# Measurement_board.net
KiCad netlist of a schematic drawn in Altium Designer
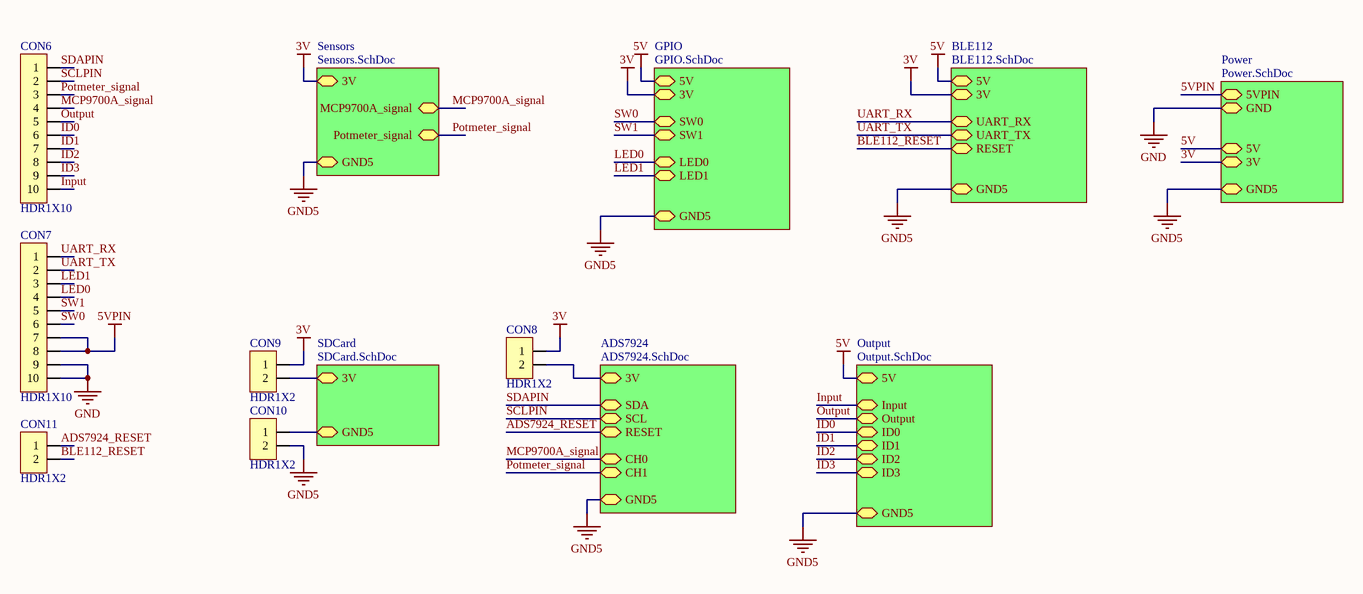
[diagram p0: Measurement_board.SchDoc]

(export (version "E")
  (design (tool "Eeschema 10.0.6"))
  (components
    (comp (ref "CON6")
      (value "HDR1X10")
      (footprint "dimploma:HDR1X10RAST")
      (libsource (lib "diploma") (part "HDR1X10"))
    )
    (comp (ref "CON7")
      (value "HDR1X10")
      (footprint "dimploma:HDR1X10RAST")
      (libsource (lib "diploma") (part "HDR1X10"))
    )
    (comp (ref "CON8")
      (value "HDR1X2")
      (footprint "dimploma:HDR1X2RAST")
      (libsource (lib "diploma") (part "HDR1X2"))
    )
    (comp (ref "CON9")
      (value "HDR1X2")
      (footprint "dimploma:HDR1X2RAST")
      (libsource (lib "diploma") (part "HDR1X2"))
    )
    (comp (ref "CON10")
      (value "HDR1X2")
      (footprint "dimploma:HDR1X2RAST")
      (libsource (lib "diploma") (part "HDR1X2"))
    )
    (comp (ref "CON11")
      (value "HDR1X2")
      (footprint "dimploma:HDR1X2RAST")
      (libsource (lib "diploma") (part "HDR1X2"))
    )
  )
  (nets
    (net (code "1") (name "/3V_1") (class "Default")
      (node (ref "CON9") (pin "2") (pinfunction "2_2") (pintype "passive"))
    )
    (net (code "2") (name "/3V_2") (class "Default")
      (node (ref "CON8") (pin "2") (pinfunction "2_2") (pintype "passive"))
    )
    (net (code "3") (name "/ADS7924_RESET") (class "Default")
      (node (ref "CON11") (pin "1") (pinfunction "1_1") (pintype "passive"))
    )
    (net (code "4") (name "/BLE112_RESET") (class "Default")
      (node (ref "CON11") (pin "2") (pinfunction "2_2") (pintype "passive"))
    )
    (net (code "5") (name "/GND5") (class "Default")
      (node (ref "CON10") (pin "1") (pinfunction "1_1") (pintype "passive"))
    )
    (net (code "6") (name "/ID0") (class "Default")
      (node (ref "CON6") (pin "6") (pinfunction "6_6") (pintype "passive"))
    )
    (net (code "7") (name "/ID1") (class "Default")
      (node (ref "CON6") (pin "7") (pinfunction "7_7") (pintype "passive"))
    )
    (net (code "8") (name "/ID2") (class "Default")
      (node (ref "CON6") (pin "8") (pinfunction "8_8") (pintype "passive"))
    )
    (net (code "9") (name "/ID3") (class "Default")
      (node (ref "CON6") (pin "9") (pinfunction "9_9") (pintype "passive"))
    )
    (net (code "10") (name "/Input") (class "Default")
      (node (ref "CON6") (pin "10") (pinfunction "10_10") (pintype "passive"))
    )
    (net (code "11") (name "/LED0") (class "Default")
      (node (ref "CON7") (pin "4") (pinfunction "4_4") (pintype "passive"))
    )
    (net (code "12") (name "/LED1") (class "Default")
      (node (ref "CON7") (pin "3") (pinfunction "3_3") (pintype "passive"))
    )
    (net (code "13") (name "/MCP9700A_signal") (class "Default")
      (node (ref "CON6") (pin "4") (pinfunction "4_4") (pintype "passive"))
    )
    (net (code "14") (name "/Output") (class "Default")
      (node (ref "CON6") (pin "5") (pinfunction "5_5") (pintype "passive"))
    )
    (net (code "15") (name "/Potmeter_signal") (class "Default")
      (node (ref "CON6") (pin "3") (pinfunction "3_3") (pintype "passive"))
    )
    (net (code "16") (name "/SCLPIN") (class "Default")
      (node (ref "CON6") (pin "2") (pinfunction "2_2") (pintype "passive"))
    )
    (net (code "17") (name "/SDAPIN") (class "Default")
      (node (ref "CON6") (pin "1") (pinfunction "1_1") (pintype "passive"))
    )
    (net (code "18") (name "/SW0") (class "Default")
      (node (ref "CON7") (pin "6") (pinfunction "6_6") (pintype "passive"))
    )
    (net (code "19") (name "/SW1") (class "Default")
      (node (ref "CON7") (pin "5") (pinfunction "5_5") (pintype "passive"))
    )
    (net (code "20") (name "/UART_RX") (class "Default")
      (node (ref "CON7") (pin "1") (pinfunction "1_1") (pintype "passive"))
    )
    (net (code "21") (name "/UART_TX") (class "Default")
      (node (ref "CON7") (pin "2") (pinfunction "2_2") (pintype "passive"))
    )
    (net (code "22") (name "3V") (class "Default")
      (node (ref "CON8") (pin "1") (pinfunction "1_1") (pintype "passive"))
      (node (ref "CON9") (pin "1") (pinfunction "1_1") (pintype "passive"))
    )
    (net (code "24") (name "5VPIN") (class "Default")
      (node (ref "CON7") (pin "7") (pinfunction "7_7") (pintype "passive"))
      (node (ref "CON7") (pin "8") (pinfunction "8_8") (pintype "passive"))
    )
    (net (code "25") (name "GND") (class "Default")
      (node (ref "CON7") (pin "10") (pinfunction "10_10") (pintype "passive"))
      (node (ref "CON7") (pin "9") (pinfunction "9_9") (pintype "passive"))
    )
    (net (code "26") (name "GND5") (class "Default")
      (node (ref "CON10") (pin "2") (pinfunction "2_2") (pintype "passive"))
    )
  )
)
